# NN22_IMU_Adapter00_s00.net
KiCad netlist of a schematic drawn in EAGLE
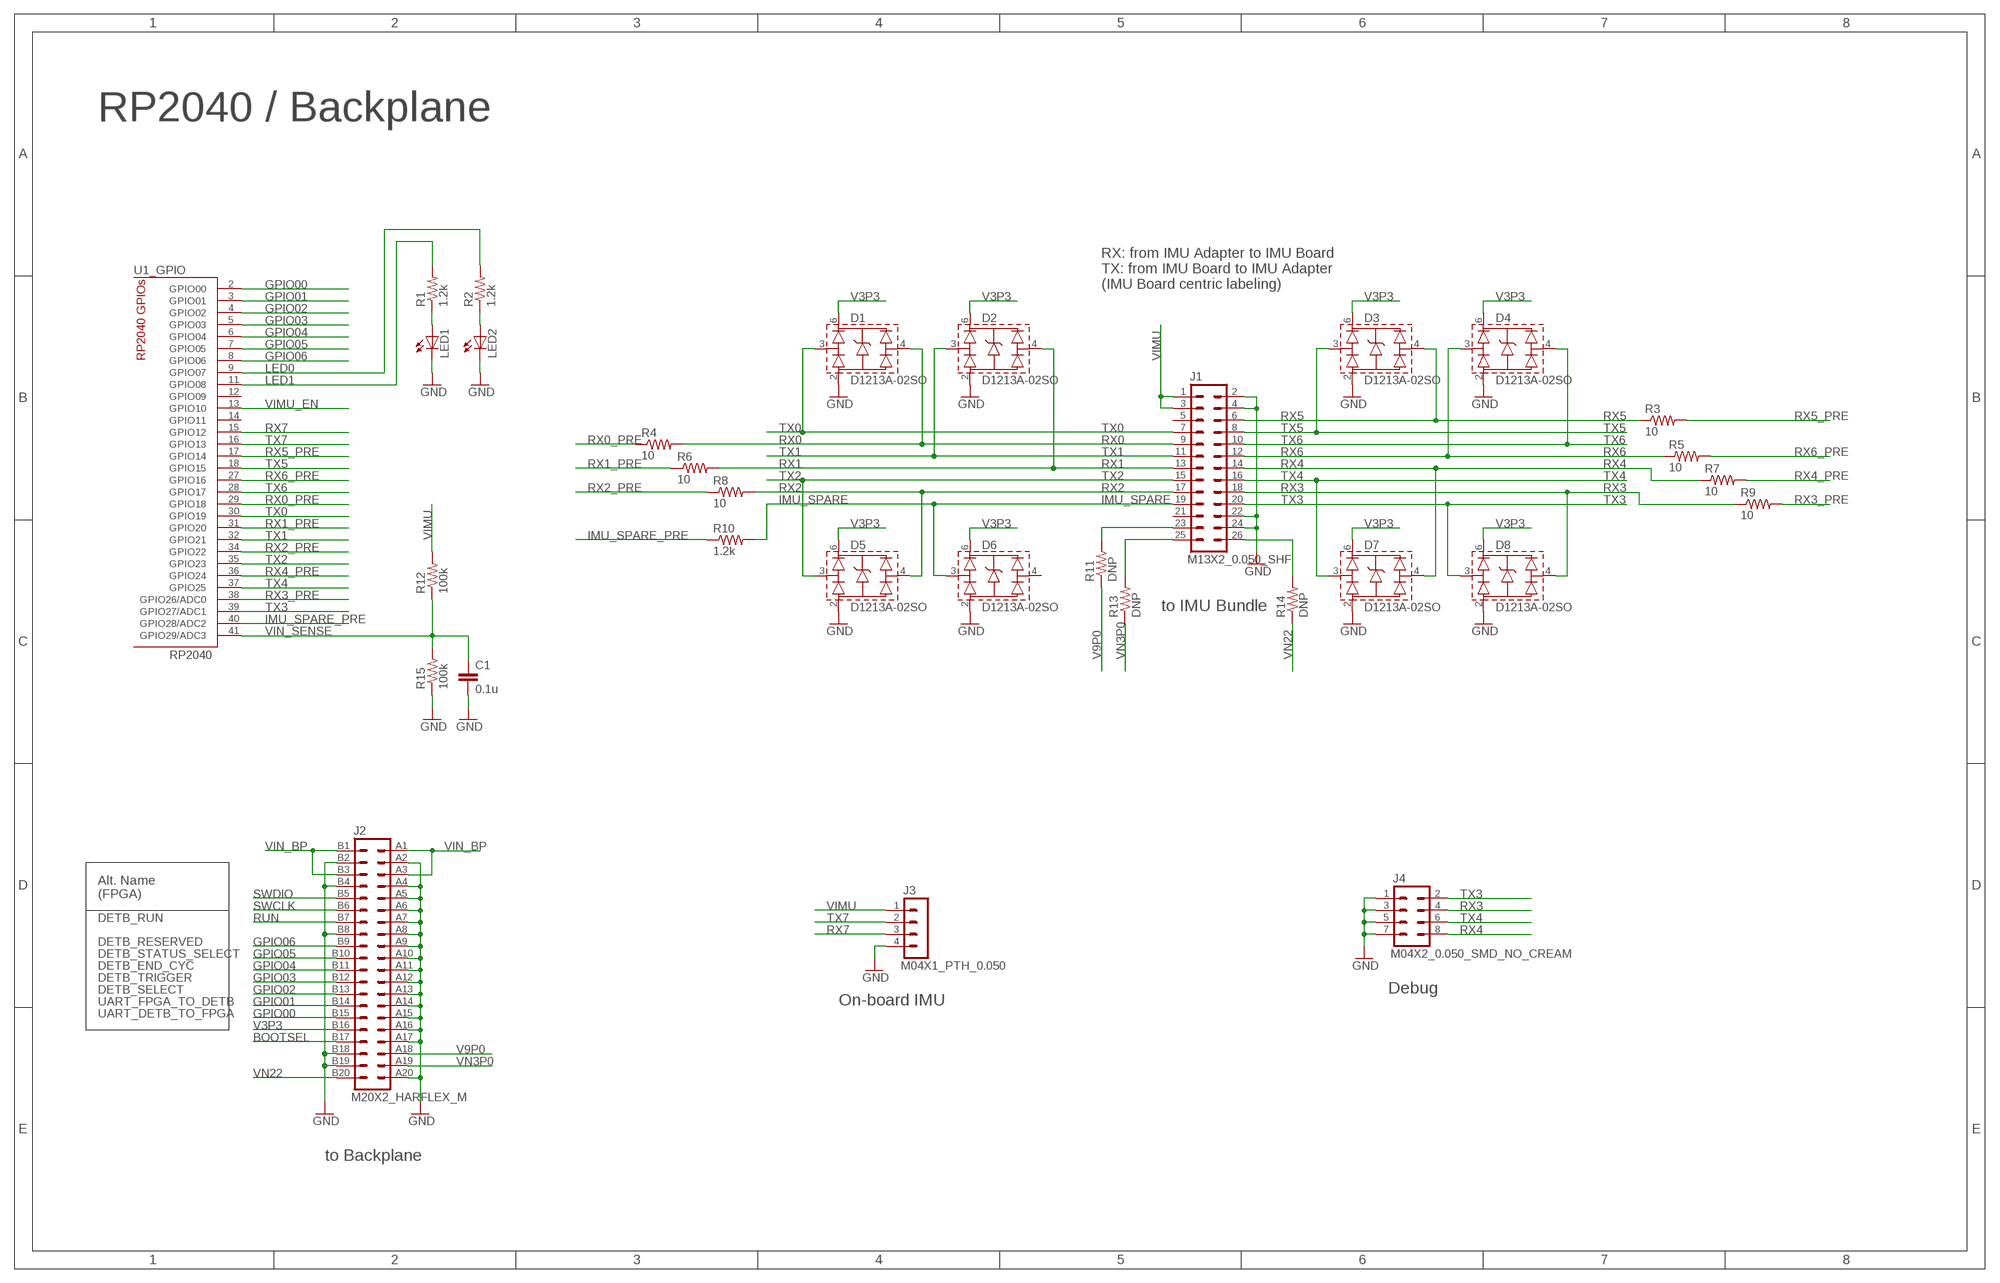
[diagram p0: schematic, sheet 1]
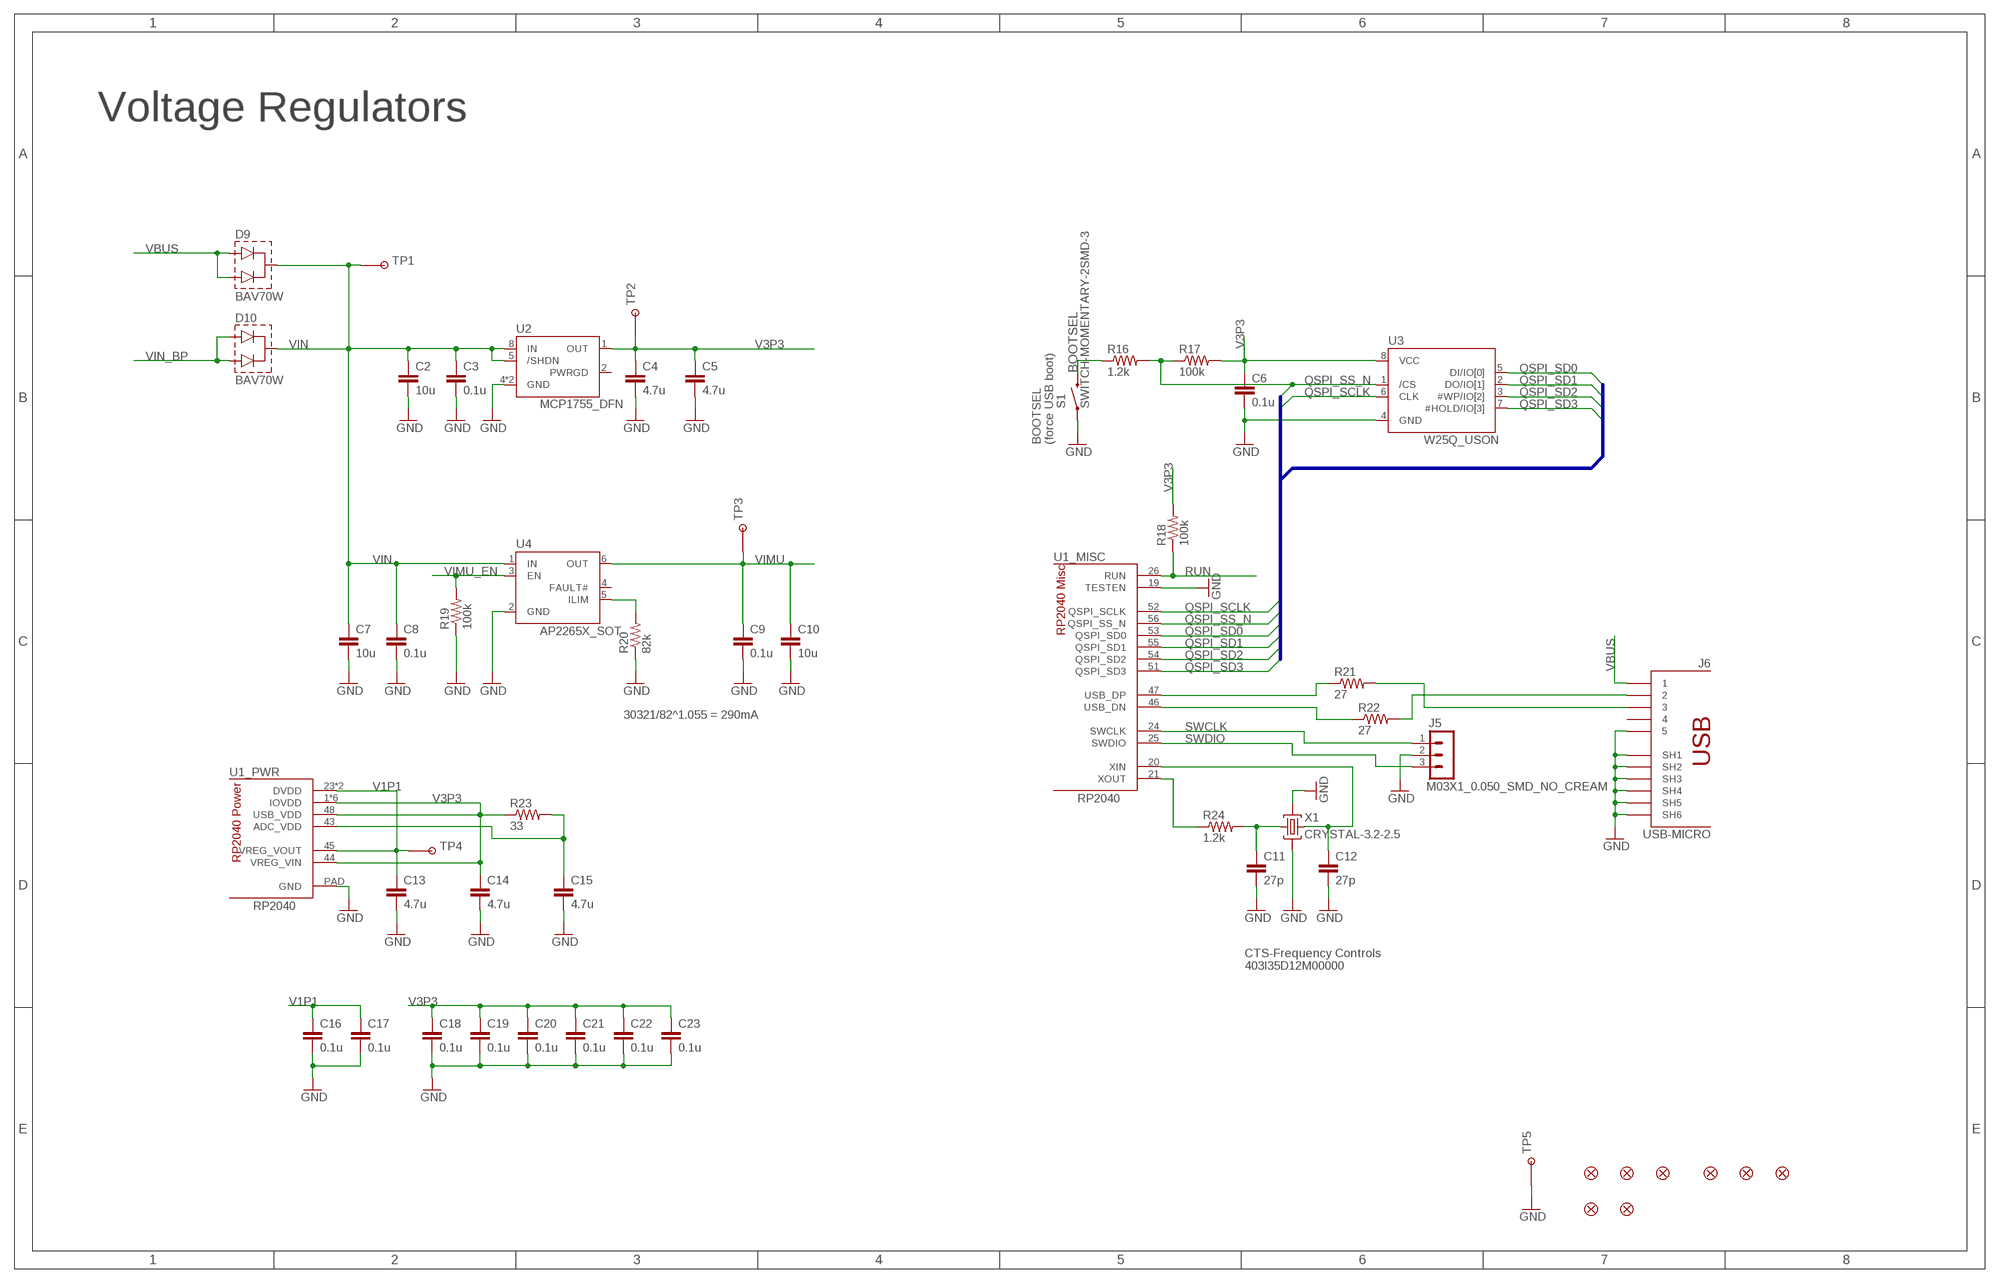
[diagram p1: schematic, sheet 2]

(export (version "E")
  (design (tool "Eeschema 10.0.6"))
  (components
    (comp (ref "C1")
      (value "0.1u")
      (footprint "eagle-import:0402-CAP")
      (libsource (lib "eagle-import") (part "CAP0402-CAP"))
    )
    (comp (ref "D1")
      (value "D1213A-02SO")
      (footprint "eagle-import:SOT23-6")
      (libsource (lib "eagle-import") (part "D1213A-02SO"))
    )
    (comp (ref "D2")
      (value "D1213A-02SO")
      (footprint "eagle-import:SOT23-6")
      (libsource (lib "eagle-import") (part "D1213A-02SO"))
    )
    (comp (ref "D3")
      (value "D1213A-02SO")
      (footprint "eagle-import:SOT23-6")
      (libsource (lib "eagle-import") (part "D1213A-02SO"))
    )
    (comp (ref "D4")
      (value "D1213A-02SO")
      (footprint "eagle-import:SOT23-6")
      (libsource (lib "eagle-import") (part "D1213A-02SO"))
    )
    (comp (ref "D5")
      (value "D1213A-02SO")
      (footprint "eagle-import:SOT23-6")
      (libsource (lib "eagle-import") (part "D1213A-02SO"))
    )
    (comp (ref "D6")
      (value "D1213A-02SO")
      (footprint "eagle-import:SOT23-6")
      (libsource (lib "eagle-import") (part "D1213A-02SO"))
    )
    (comp (ref "D7")
      (value "D1213A-02SO")
      (footprint "eagle-import:SOT23-6")
      (libsource (lib "eagle-import") (part "D1213A-02SO"))
    )
    (comp (ref "D8")
      (value "D1213A-02SO")
      (footprint "eagle-import:SOT23-6")
      (libsource (lib "eagle-import") (part "D1213A-02SO"))
    )
    (comp (ref "J1")
      (value "M13X2_0.050_SHF")
      (footprint "eagle-import:M13X2_0.050_SHF")
      (libsource (lib "eagle-import") (part "M13X2_0.050_SHF"))
    )
    (comp (ref "J2")
      (value "M20X2_HARFLEX_M")
      (footprint "eagle-import:M20X2_HARFLEX_M")
      (libsource (lib "eagle-import") (part "M20X2_HARFLEX_M"))
    )
    (comp (ref "J3")
      (value "M04X1_PTH_0.050")
      (footprint "eagle-import:M04X1_0.050_PTH")
      (libsource (lib "eagle-import") (part "M04X1_PTH_0.050"))
    )
    (comp (ref "J4")
      (value "M04X2_0.050_SMD_NO_CREAM")
      (footprint "eagle-import:M04X2_0.050_SMD_NO_CREAM")
      (libsource (lib "eagle-import") (part "M04X2_0.050_SMD_NO_CREAM"))
    )
    (comp (ref "LED1")
      (value "LED0603")
      (footprint "eagle-import:LED-0603")
      (libsource (lib "eagle-import") (part "LED0603"))
    )
    (comp (ref "LED2")
      (value "LED0603")
      (footprint "eagle-import:LED-0603")
      (libsource (lib "eagle-import") (part "LED0603"))
    )
    (comp (ref "R1")
      (value "1.2k")
      (footprint "eagle-import:0402-RES")
      (libsource (lib "eagle-import") (part "RESISTOR0402-RES"))
    )
    (comp (ref "R2")
      (value "1.2k")
      (footprint "eagle-import:0402-RES")
      (libsource (lib "eagle-import") (part "RESISTOR0402-RES"))
    )
    (comp (ref "R3")
      (value "10")
      (footprint "eagle-import:0402-RES")
      (libsource (lib "eagle-import") (part "RESISTOR0402-RES"))
    )
    (comp (ref "R4")
      (value "10")
      (footprint "eagle-import:0402-RES")
      (libsource (lib "eagle-import") (part "RESISTOR0402-RES"))
    )
    (comp (ref "R5")
      (value "10")
      (footprint "eagle-import:0402-RES")
      (libsource (lib "eagle-import") (part "RESISTOR0402-RES"))
    )
    (comp (ref "R6")
      (value "10")
      (footprint "eagle-import:0402-RES")
      (libsource (lib "eagle-import") (part "RESISTOR0402-RES"))
    )
    (comp (ref "R7")
      (value "10")
      (footprint "eagle-import:0402-RES")
      (libsource (lib "eagle-import") (part "RESISTOR0402-RES"))
    )
    (comp (ref "R8")
      (value "10")
      (footprint "eagle-import:0402-RES")
      (libsource (lib "eagle-import") (part "RESISTOR0402-RES"))
    )
    (comp (ref "R9")
      (value "10")
      (footprint "eagle-import:0402-RES")
      (libsource (lib "eagle-import") (part "RESISTOR0402-RES"))
    )
    (comp (ref "R10")
      (value "1.2k")
      (footprint "eagle-import:0402-RES")
      (libsource (lib "eagle-import") (part "RESISTOR0402-RES"))
    )
    (comp (ref "R11")
      (value "DNP")
      (footprint "eagle-import:0603-RES")
      (libsource (lib "eagle-import") (part "RESISTOR0603-RES"))
    )
    (comp (ref "R12")
      (value "100k")
      (footprint "eagle-import:0402-RES")
      (libsource (lib "eagle-import") (part "RESISTOR0402-RES"))
    )
    (comp (ref "R13")
      (value "DNP")
      (footprint "eagle-import:0603-RES")
      (libsource (lib "eagle-import") (part "RESISTOR0603-RES"))
    )
    (comp (ref "R14")
      (value "DNP")
      (footprint "eagle-import:0603-RES")
      (libsource (lib "eagle-import") (part "RESISTOR0603-RES"))
    )
    (comp (ref "R15")
      (value "100k")
      (footprint "eagle-import:0402-RES")
      (libsource (lib "eagle-import") (part "RESISTOR0402-RES"))
    )
    (comp (ref "U1")
      (value "RP2040")
      (footprint "eagle-import:QFN-56_EP")
      (libsource (lib "eagle-import") (part "RP2040"))
    )
    (comp (ref "C2")
      (value "10u")
      (footprint "eagle-import:0603-CAP")
      (libsource (lib "eagle-import") (part "CAP0603-CAP"))
    )
    (comp (ref "C3")
      (value "0.1u")
      (footprint "eagle-import:0402-CAP")
      (libsource (lib "eagle-import") (part "CAP0402-CAP"))
    )
    (comp (ref "C4")
      (value "4.7u")
      (footprint "eagle-import:0402-CAP")
      (libsource (lib "eagle-import") (part "CAP0402-CAP"))
    )
    (comp (ref "C5")
      (value "4.7u")
      (footprint "eagle-import:0402-CAP")
      (libsource (lib "eagle-import") (part "CAP0402-CAP"))
    )
    (comp (ref "C6")
      (value "0.1u")
      (footprint "eagle-import:0402-CAP")
      (libsource (lib "eagle-import") (part "CAP0402-CAP"))
    )
    (comp (ref "C7")
      (value "10u")
      (footprint "eagle-import:0603-CAP")
      (libsource (lib "eagle-import") (part "CAP0603-CAP"))
    )
    (comp (ref "C8")
      (value "0.1u")
      (footprint "eagle-import:0402-CAP")
      (libsource (lib "eagle-import") (part "CAP0402-CAP"))
    )
    (comp (ref "C9")
      (value "0.1u")
      (footprint "eagle-import:0402-CAP")
      (libsource (lib "eagle-import") (part "CAP0402-CAP"))
    )
    (comp (ref "C10")
      (value "10u")
      (footprint "eagle-import:0603-CAP")
      (libsource (lib "eagle-import") (part "CAP0603-CAP"))
    )
    (comp (ref "C11")
      (value "27p")
      (footprint "eagle-import:0402-CAP")
      (libsource (lib "eagle-import") (part "CAP0402-CAP"))
    )
    (comp (ref "C12")
      (value "27p")
      (footprint "eagle-import:0402-CAP")
      (libsource (lib "eagle-import") (part "CAP0402-CAP"))
    )
    (comp (ref "C13")
      (value "4.7u")
      (footprint "eagle-import:0402-CAP")
      (libsource (lib "eagle-import") (part "CAP0402-CAP"))
    )
    (comp (ref "C14")
      (value "4.7u")
      (footprint "eagle-import:0402-CAP")
      (libsource (lib "eagle-import") (part "CAP0402-CAP"))
    )
    (comp (ref "C15")
      (value "4.7u")
      (footprint "eagle-import:0402-CAP")
      (libsource (lib "eagle-import") (part "CAP0402-CAP"))
    )
    (comp (ref "C16")
      (value "0.1u")
      (footprint "eagle-import:0402-CAP")
      (libsource (lib "eagle-import") (part "CAP0402-CAP"))
    )
    (comp (ref "C17")
      (value "0.1u")
      (footprint "eagle-import:0402-CAP")
      (libsource (lib "eagle-import") (part "CAP0402-CAP"))
    )
    (comp (ref "C18")
      (value "0.1u")
      (footprint "eagle-import:0402-CAP")
      (libsource (lib "eagle-import") (part "CAP0402-CAP"))
    )
    (comp (ref "C19")
      (value "0.1u")
      (footprint "eagle-import:0402-CAP")
      (libsource (lib "eagle-import") (part "CAP0402-CAP"))
    )
    (comp (ref "C20")
      (value "0.1u")
      (footprint "eagle-import:0402-CAP")
      (libsource (lib "eagle-import") (part "CAP0402-CAP"))
    )
    (comp (ref "C21")
      (value "0.1u")
      (footprint "eagle-import:0402-CAP")
      (libsource (lib "eagle-import") (part "CAP0402-CAP"))
    )
    (comp (ref "C22")
      (value "0.1u")
      (footprint "eagle-import:0402-CAP")
      (libsource (lib "eagle-import") (part "CAP0402-CAP"))
    )
    (comp (ref "C23")
      (value "0.1u")
      (footprint "eagle-import:0402-CAP")
      (libsource (lib "eagle-import") (part "CAP0402-CAP"))
    )
    (comp (ref "D9")
      (value "BAV70W")
      (footprint "eagle-import:SOT323")
      (libsource (lib "eagle-import") (part "DIODE-COMMON_CATHODE_SOT323"))
    )
    (comp (ref "D10")
      (value "BAV70W")
      (footprint "eagle-import:SOT323")
      (libsource (lib "eagle-import") (part "DIODE-COMMON_CATHODE_SOT323"))
    )
    (comp (ref "FID1")
      (value "FIDUCIALUFIDUCIAL")
      (footprint "eagle-import:MICRO-FIDUCIAL")
      (libsource (lib "eagle-import") (part "FIDUCIALUFIDUCIAL"))
    )
    (comp (ref "FID2")
      (value "FIDUCIALUFIDUCIAL")
      (footprint "eagle-import:MICRO-FIDUCIAL")
      (libsource (lib "eagle-import") (part "FIDUCIALUFIDUCIAL"))
    )
    (comp (ref "FID3")
      (value "FIDUCIALUFIDUCIAL")
      (footprint "eagle-import:MICRO-FIDUCIAL")
      (libsource (lib "eagle-import") (part "FIDUCIALUFIDUCIAL"))
    )
    (comp (ref "FID4")
      (value "FIDUCIALUFIDUCIAL")
      (footprint "eagle-import:MICRO-FIDUCIAL")
      (libsource (lib "eagle-import") (part "FIDUCIALUFIDUCIAL"))
    )
    (comp (ref "FID5")
      (value "FIDUCIALUFIDUCIAL")
      (footprint "eagle-import:MICRO-FIDUCIAL")
      (libsource (lib "eagle-import") (part "FIDUCIALUFIDUCIAL"))
    )
    (comp (ref "FID6")
      (value "FIDUCIALUFIDUCIAL")
      (footprint "eagle-import:MICRO-FIDUCIAL")
      (libsource (lib "eagle-import") (part "FIDUCIALUFIDUCIAL"))
    )
    (comp (ref "FID7")
      (value "FIDUCIALUFIDUCIAL")
      (footprint "eagle-import:MICRO-FIDUCIAL")
      (libsource (lib "eagle-import") (part "FIDUCIALUFIDUCIAL"))
    )
    (comp (ref "FID8")
      (value "FIDUCIALUFIDUCIAL")
      (footprint "eagle-import:MICRO-FIDUCIAL")
      (libsource (lib "eagle-import") (part "FIDUCIALUFIDUCIAL"))
    )
    (comp (ref "J5")
      (value "M03X1_0.050_SMD_NO_CREAM")
      (footprint "eagle-import:M03X1_0.050_SMD_NO_CREAM")
      (libsource (lib "eagle-import") (part "M03X1_0.050_SMD_NO_CREAM"))
    )
    (comp (ref "J6")
      (value "USB-MICRO")
      (footprint "eagle-import:USB-MICRO")
      (libsource (lib "eagle-import") (part "USB-MICRO"))
    )
    (comp (ref "R16")
      (value "1.2k")
      (footprint "eagle-import:0402-RES")
      (libsource (lib "eagle-import") (part "RESISTOR0402-RES"))
    )
    (comp (ref "R17")
      (value "100k")
      (footprint "eagle-import:0402-RES")
      (libsource (lib "eagle-import") (part "RESISTOR0402-RES"))
    )
    (comp (ref "R18")
      (value "100k")
      (footprint "eagle-import:0402-RES")
      (libsource (lib "eagle-import") (part "RESISTOR0402-RES"))
    )
    (comp (ref "R19")
      (value "100k")
      (footprint "eagle-import:0402-RES")
      (libsource (lib "eagle-import") (part "RESISTOR0402-RES"))
    )
    (comp (ref "R20")
      (value "82k")
      (footprint "eagle-import:0402-RES")
      (libsource (lib "eagle-import") (part "RESISTOR0402-RES"))
    )
    (comp (ref "R21")
      (value "27")
      (footprint "eagle-import:0402-RES")
      (libsource (lib "eagle-import") (part "RESISTOR0402-RES"))
    )
    (comp (ref "R22")
      (value "27")
      (footprint "eagle-import:0402-RES")
      (libsource (lib "eagle-import") (part "RESISTOR0402-RES"))
    )
    (comp (ref "R23")
      (value "33")
      (footprint "eagle-import:0402-RES")
      (libsource (lib "eagle-import") (part "RESISTOR0402-RES"))
    )
    (comp (ref "R24")
      (value "1.2k")
      (footprint "eagle-import:0402-RES")
      (libsource (lib "eagle-import") (part "RESISTOR0402-RES"))
    )
    (comp (ref "S1")
      (value "SWITCH-MOMENTARY-2SMD-3")
      (footprint "eagle-import:TACTILE_SWITCH_SMD-3")
      (libsource (lib "eagle-import") (part "SWITCH-MOMENTARY-2SMD-3"))
    )
    (comp (ref "TP1")
      (value "TESTPOINT_ROUND")
      (footprint "eagle-import:TESTPAD_ROUND")
      (libsource (lib "eagle-import") (part "TESTPOINT_ROUND"))
    )
    (comp (ref "TP2")
      (value "TESTPOINT_ROUND")
      (footprint "eagle-import:TESTPAD_ROUND")
      (libsource (lib "eagle-import") (part "TESTPOINT_ROUND"))
    )
    (comp (ref "TP3")
      (value "TESTPOINT_ROUND")
      (footprint "eagle-import:TESTPAD_ROUND")
      (libsource (lib "eagle-import") (part "TESTPOINT_ROUND"))
    )
    (comp (ref "TP4")
      (value "TESTPOINTPADSMALL")
      (footprint "eagle-import:TESTPAD_SMALL")
      (libsource (lib "eagle-import") (part "TESTPOINTPADSMALL"))
    )
    (comp (ref "TP5")
      (value "TESTPOINT1X01")
      (footprint "eagle-import:1X01")
      (libsource (lib "eagle-import") (part "TESTPOINT1X01"))
    )
    (comp (ref "U2")
      (value "MCP1755_DFN")
      (footprint "eagle-import:DFN8_2X3MM")
      (libsource (lib "eagle-import") (part "MCP1755_DFN"))
    )
    (comp (ref "U3")
      (value "W25Q_USON")
      (footprint "eagle-import:USON8L-2X3MM")
      (libsource (lib "eagle-import") (part "W25Q_USON"))
    )
    (comp (ref "U4")
      (value "AP2265X_SOT")
      (footprint "eagle-import:SOT23-6")
      (libsource (lib "eagle-import") (part "AP2265X_SOT"))
    )
    (comp (ref "X1")
      (value "CRYSTAL-3.2-2.5")
      (footprint "eagle-import:CRYSTAL-3.2-2.5")
      (libsource (lib "eagle-import") (part "CRYSTAL-3.2-2.5"))
    )
  )
  (nets
    (net (code "1") (name "BOOTSEL") (class "Default")
      (node (ref "J2") (pin "B17") (pinfunction "33_B17") (pintype "passive"))
      (node (ref "R16") (pin "1") (pinfunction "1_1") (pintype "passive"))
      (node (ref "S1") (pin "4") (pinfunction "2_4") (pintype "passive"))
    )
    (net (code "2") (name "GND") (class "Default")
      (node (ref "C1") (pin "2") (pinfunction "2_2") (pintype "passive"))
      (node (ref "C10") (pin "2") (pinfunction "2_2") (pintype "passive"))
      (node (ref "C11") (pin "2") (pinfunction "2_2") (pintype "passive"))
      (node (ref "C12") (pin "2") (pinfunction "2_2") (pintype "passive"))
      (node (ref "C13") (pin "2") (pinfunction "2_2") (pintype "passive"))
      (node (ref "C14") (pin "2") (pinfunction "2_2") (pintype "passive"))
      (node (ref "C15") (pin "2") (pinfunction "2_2") (pintype "passive"))
      (node (ref "C16") (pin "2") (pinfunction "2_2") (pintype "passive"))
      (node (ref "C17") (pin "2") (pinfunction "2_2") (pintype "passive"))
      (node (ref "C18") (pin "2") (pinfunction "2_2") (pintype "passive"))
      (node (ref "C19") (pin "2") (pinfunction "2_2") (pintype "passive"))
      (node (ref "C2") (pin "2") (pinfunction "2_2") (pintype "passive"))
      (node (ref "C20") (pin "2") (pinfunction "2_2") (pintype "passive"))
      (node (ref "C21") (pin "2") (pinfunction "2_2") (pintype "passive"))
      (node (ref "C22") (pin "2") (pinfunction "2_2") (pintype "passive"))
      (node (ref "C23") (pin "2") (pinfunction "2_2") (pintype "passive"))
      (node (ref "C3") (pin "2") (pinfunction "2_2") (pintype "passive"))
      (node (ref "C4") (pin "2") (pinfunction "2_2") (pintype "passive"))
      (node (ref "C5") (pin "2") (pinfunction "2_2") (pintype "passive"))
      (node (ref "C6") (pin "2") (pinfunction "2_2") (pintype "passive"))
      (node (ref "C7") (pin "2") (pinfunction "2_2") (pintype "passive"))
      (node (ref "C8") (pin "2") (pinfunction "2_2") (pintype "passive"))
      (node (ref "C9") (pin "2") (pinfunction "2_2") (pintype "passive"))
      (node (ref "D1") (pin "2") (pinfunction "VN_2") (pintype "power_in"))
      (node (ref "D2") (pin "2") (pinfunction "VN_2") (pintype "power_in"))
      (node (ref "D3") (pin "2") (pinfunction "VN_2") (pintype "power_in"))
      (node (ref "D4") (pin "2") (pinfunction "VN_2") (pintype "power_in"))
      (node (ref "D5") (pin "2") (pinfunction "VN_2") (pintype "power_in"))
      (node (ref "D6") (pin "2") (pinfunction "VN_2") (pintype "power_in"))
      (node (ref "D7") (pin "2") (pinfunction "VN_2") (pintype "power_in"))
      (node (ref "D8") (pin "2") (pinfunction "VN_2") (pintype "power_in"))
      (node (ref "J1") (pin "2") (pinfunction "2_2") (pintype "passive"))
      (node (ref "J1") (pin "22") (pinfunction "22_22") (pintype "passive"))
      (node (ref "J1") (pin "24") (pinfunction "24_24") (pintype "passive"))
      (node (ref "J1") (pin "4") (pinfunction "4_4") (pintype "passive"))
      (node (ref "J2") (pin "A10") (pinfunction "20_A10") (pintype "passive"))
      (node (ref "J2") (pin "A11") (pinfunction "22_A11") (pintype "passive"))
      (node (ref "J2") (pin "A12") (pinfunction "24_A12") (pintype "passive"))
      (node (ref "J2") (pin "A13") (pinfunction "26_A13") (pintype "passive"))
      (node (ref "J2") (pin "A14") (pinfunction "28_A14") (pintype "passive"))
      (node (ref "J2") (pin "A15") (pinfunction "30_A15") (pintype "passive"))
      (node (ref "J2") (pin "A16") (pinfunction "32_A16") (pintype "passive"))
      (node (ref "J2") (pin "A17") (pinfunction "34_A17") (pintype "passive"))
      (node (ref "J2") (pin "A2") (pinfunction "4_A2") (pintype "passive"))
      (node (ref "J2") (pin "A20") (pinfunction "40_A20") (pintype "passive"))
      (node (ref "J2") (pin "A4") (pinfunction "8_A4") (pintype "passive"))
      (node (ref "J2") (pin "A5") (pinfunction "10_A5") (pintype "passive"))
      (node (ref "J2") (pin "A6") (pinfunction "12_A6") (pintype "passive"))
      (node (ref "J2") (pin "A7") (pinfunction "14_A7") (pintype "passive"))
      (node (ref "J2") (pin "A8") (pinfunction "16_A8") (pintype "passive"))
      (node (ref "J2") (pin "A9") (pinfunction "18_A9") (pintype "passive"))
      (node (ref "J2") (pin "B18") (pinfunction "35_B18") (pintype "passive"))
      (node (ref "J2") (pin "B19") (pinfunction "37_B19") (pintype "passive"))
      (node (ref "J2") (pin "B2") (pinfunction "3_B2") (pintype "passive"))
      (node (ref "J2") (pin "B4") (pinfunction "7_B4") (pintype "passive"))
      (node (ref "J2") (pin "B8") (pinfunction "15_B8") (pintype "passive"))
      (node (ref "J3") (pin "4") (pinfunction "4_4") (pintype "passive"))
      (node (ref "J4") (pin "1") (pinfunction "1_1") (pintype "passive"))
      (node (ref "J4") (pin "3") (pinfunction "3_3") (pintype "passive"))
      (node (ref "J4") (pin "5") (pinfunction "5_5") (pintype "passive"))
      (node (ref "J4") (pin "7") (pinfunction "7_7") (pintype "passive"))
      (node (ref "J5") (pin "2") (pinfunction "2_2") (pintype "passive"))
      (node (ref "J6") (pin "5") (pinfunction "5_5") (pintype "bidirectional"))
      (node (ref "J6") (pin "SH1") (pinfunction "SH1_SH1") (pintype "bidirectional"))
      (node (ref "J6") (pin "SH2") (pinfunction "SH2_SH2") (pintype "bidirectional"))
      (node (ref "J6") (pin "SH3") (pinfunction "SH3_SH3") (pintype "bidirectional"))
      (node (ref "J6") (pin "SH4") (pinfunction "SH4_SH4") (pintype "bidirectional"))
      (node (ref "J6") (pin "SH5") (pinfunction "SH5_SH5") (pintype "bidirectional"))
      (node (ref "J6") (pin "SH6") (pinfunction "SH6_SH6") (pintype "bidirectional"))
      (node (ref "LED1") (pin "C") (pinfunction "C_C") (pintype "passive"))
      (node (ref "LED2") (pin "C") (pinfunction "C_C") (pintype "passive"))
      (node (ref "R15") (pin "1") (pinfunction "1_1") (pintype "passive"))
      (node (ref "R19") (pin "1") (pinfunction "1_1") (pintype "passive"))
      (node (ref "R20") (pin "1") (pinfunction "1_1") (pintype "passive"))
      (node (ref "S1") (pin "1") (pinfunction "1_1") (pintype "passive"))
      (node (ref "TP5") (pin "1") (pinfunction "P$1_1") (pintype "bidirectional"))
      (node (ref "U1") (pin "19") (pinfunction "TESTEN_19") (pintype "input"))
      (node (ref "U1") (pin "PAD") (pinfunction "GND_PAD") (pintype "power_in"))
      (node (ref "U2") (pin "4") (pinfunction "GND_4") (pintype "power_in"))
      (node (ref "U2") (pin "P") (pinfunction "GND_P") (pintype "power_in"))
      (node (ref "U3") (pin "4") (pinfunction "GND_4") (pintype "power_in"))
      (node (ref "U4") (pin "2") (pinfunction "GND_2") (pintype "power_in"))
      (node (ref "X1") (pin "2") (pinfunction "GND_2") (pintype "passive"))
      (node (ref "X1") (pin "4") (pinfunction "GND_4") (pintype "passive"))
    )
    (net (code "3") (name "GPIO00") (class "Default")
      (node (ref "J2") (pin "B15") (pinfunction "29_B15") (pintype "passive"))
      (node (ref "U1") (pin "2") (pinfunction "GPIO00_2") (pintype "bidirectional"))
    )
    (net (code "4") (name "GPIO01") (class "Default")
      (node (ref "J2") (pin "B14") (pinfunction "27_B14") (pintype "passive"))
      (node (ref "U1") (pin "3") (pinfunction "GPIO01_3") (pintype "bidirectional"))
    )
    (net (code "5") (name "GPIO02") (class "Default")
      (node (ref "J2") (pin "B13") (pinfunction "25_B13") (pintype "passive"))
      (node (ref "U1") (pin "4") (pinfunction "GPIO02_4") (pintype "bidirectional"))
    )
    (net (code "6") (name "GPIO03") (class "Default")
      (node (ref "J2") (pin "B12") (pinfunction "23_B12") (pintype "passive"))
      (node (ref "U1") (pin "5") (pinfunction "GPIO03_5") (pintype "bidirectional"))
    )
    (net (code "7") (name "GPIO04") (class "Default")
      (node (ref "J2") (pin "B11") (pinfunction "21_B11") (pintype "passive"))
      (node (ref "U1") (pin "6") (pinfunction "GPIO04_6") (pintype "bidirectional"))
    )
    (net (code "8") (name "GPIO05") (class "Default")
      (node (ref "J2") (pin "B10") (pinfunction "19_B10") (pintype "passive"))
      (node (ref "U1") (pin "7") (pinfunction "GPIO05_7") (pintype "bidirectional"))
    )
    (net (code "9") (name "GPIO06") (class "Default")
      (node (ref "J2") (pin "B9") (pinfunction "17_B9") (pintype "passive"))
      (node (ref "U1") (pin "8") (pinfunction "GPIO06_8") (pintype "bidirectional"))
    )
    (net (code "10") (name "IMU_SPARE") (class "Default")
      (node (ref "D6") (pin "3") (pinfunction "CH1_3") (pintype "bidirectional"))
      (node (ref "J1") (pin "19") (pinfunction "19_19") (pintype "passive"))
      (node (ref "R10") (pin "2") (pinfunction "2_2") (pintype "passive"))
    )
    (net (code "11") (name "IMU_SPARE_PRE") (class "Default")
      (node (ref "R10") (pin "1") (pinfunction "1_1") (pintype "passive"))
      (node (ref "U1") (pin "40") (pinfunction "GPIO28/ADC2_40") (pintype "bidirectional"))
    )
    (net (code "12") (name "LED0") (class "Default")
      (node (ref "R2") (pin "2") (pinfunction "2_2") (pintype "passive"))
      (node (ref "U1") (pin "9") (pinfunction "GPIO07_9") (pintype "bidirectional"))
    )
    (net (code "13") (name "LED1") (class "Default")
      (node (ref "R1") (pin "2") (pinfunction "2_2") (pintype "passive"))
      (node (ref "U1") (pin "11") (pinfunction "GPIO08_11") (pintype "bidirectional"))
    )
    (net (code "14") (name "Net-(J1-Pad23)") (class "Default")
      (node (ref "J1") (pin "23") (pinfunction "23_23") (pintype "passive"))
      (node (ref "R11") (pin "2") (pinfunction "2_2") (pintype "passive"))
    )
    (net (code "15") (name "Net-(J1-Pad25)") (class "Default")
      (node (ref "J1") (pin "25") (pinfunction "25_25") (pintype "passive"))
      (node (ref "R13") (pin "2") (pinfunction "2_2") (pintype "passive"))
    )
    (net (code "16") (name "Net-(J1-Pad26)") (class "Default")
      (node (ref "J1") (pin "26") (pinfunction "26_26") (pintype "passive"))
      (node (ref "R14") (pin "2") (pinfunction "2_2") (pintype "passive"))
    )
    (net (code "17") (name "Net-(J6-Pad2)") (class "Default")
      (node (ref "J6") (pin "2") (pinfunction "2_2") (pintype "bidirectional"))
      (node (ref "R22") (pin "2") (pinfunction "2_2") (pintype "passive"))
    )
    (net (code "18") (name "Net-(J6-Pad3)") (class "Default")
      (node (ref "J6") (pin "3") (pinfunction "3_3") (pintype "bidirectional"))
      (node (ref "R21") (pin "2") (pinfunction "2_2") (pintype "passive"))
    )
    (net (code "19") (name "Net-(LED1-PadA)") (class "Default")
      (node (ref "LED1") (pin "A") (pinfunction "A_A") (pintype "passive"))
      (node (ref "R1") (pin "1") (pinfunction "1_1") (pintype "passive"))
    )
    (net (code "20") (name "Net-(LED2-PadA)") (class "Default")
      (node (ref "LED2") (pin "A") (pinfunction "A_A") (pintype "passive"))
      (node (ref "R2") (pin "1") (pinfunction "1_1") (pintype "passive"))
    )
    (net (code "21") (name "Net-(U1B-USB_DN)") (class "Default")
      (node (ref "R22") (pin "1") (pinfunction "1_1") (pintype "passive"))
      (node (ref "U1") (pin "46") (pinfunction "USB_DN_46") (pintype "bidirectional"))
    )
    (net (code "22") (name "Net-(U1B-USB_DP)") (class "Default")
      (node (ref "R21") (pin "1") (pinfunction "1_1") (pintype "passive"))
      (node (ref "U1") (pin "47") (pinfunction "USB_DP_47") (pintype "bidirectional"))
    )
    (net (code "23") (name "Net-(U1B-XIN)") (class "Default")
      (node (ref "C12") (pin "1") (pinfunction "1_1") (pintype "passive"))
      (node (ref "U1") (pin "20") (pinfunction "XIN_20") (pintype "bidirectional"))
      (node (ref "X1") (pin "3") (pinfunction "C2_3") (pintype "passive"))
    )
    (net (code "24") (name "Net-(U1B-XOUT)") (class "Default")
      (node (ref "R24") (pin "1") (pinfunction "1_1") (pintype "passive"))
      (node (ref "U1") (pin "21") (pinfunction "XOUT_21") (pintype "bidirectional"))
    )
    (net (code "25") (name "Net-(U1C-ADC_VDD)") (class "Default")
      (node (ref "C15") (pin "1") (pinfunction "1_1") (pintype "passive"))
      (node (ref "R23") (pin "2") (pinfunction "2_2") (pintype "passive"))
      (node (ref "U1") (pin "43") (pinfunction "ADC_VDD_43") (pintype "power_in"))
    )
    (net (code "26") (name "Net-(U4-ILIM)") (class "Default")
      (node (ref "R20") (pin "2") (pinfunction "2_2") (pintype "passive"))
      (node (ref "U4") (pin "5") (pinfunction "ILIM_5") (pintype "bidirectional"))
    )
    (net (code "27") (name "Net-(X1-C1)") (class "Default")
      (node (ref "C11") (pin "1") (pinfunction "1_1") (pintype "passive"))
      (node (ref "R24") (pin "2") (pinfunction "2_2") (pintype "passive"))
      (node (ref "X1") (pin "1") (pinfunction "C1_1") (pintype "passive"))
    )
    (net (code "28") (name "QSPI_SCLK") (class "Default")
      (node (ref "U1") (pin "52") (pinfunction "QSPI_SCLK_52") (pintype "output"))
      (node (ref "U3") (pin "6") (pinfunction "CLK_6") (pintype "input"))
    )
    (net (code "29") (name "QSPI_SD0") (class "Default")
      (node (ref "U1") (pin "53") (pinfunction "QSPI_SD0_53") (pintype "bidirectional"))
      (node (ref "U3") (pin "5") (pinfunction "DI/IO[0]_5") (pintype "bidirectional"))
    )
    (net (code "30") (name "QSPI_SD1") (class "Default")
      (node (ref "U1") (pin "55") (pinfunction "QSPI_SD1_55") (pintype "bidirectional"))
      (node (ref "U3") (pin "2") (pinfunction "DO/IO[1]_2") (pintype "bidirectional"))
    )
    (net (code "31") (name "QSPI_SD2") (class "Default")
      (node (ref "U1") (pin "54") (pinfunction "QSPI_SD2_54") (pintype "bidirectional"))
      (node (ref "U3") (pin "3") (pinfunction "#WP/IO[2]_3") (pintype "bidirectional"))
    )
    (net (code "32") (name "QSPI_SD3") (class "Default")
      (node (ref "U1") (pin "51") (pinfunction "QSPI_SD3_51") (pintype "bidirectional"))
      (node (ref "U3") (pin "7") (pinfunction "#HOLD/IO[3]_7") (pintype "bidirectional"))
    )
    (net (code "33") (name "QSPI_SS_N") (class "Default")
      (node (ref "R16") (pin "2") (pinfunction "2_2") (pintype "passive"))
      (node (ref "R17") (pin "1") (pinfunction "1_1") (pintype "passive"))
      (node (ref "U1") (pin "56") (pinfunction "QSPI_SS_N_56") (pintype "output"))
      (node (ref "U3") (pin "1") (pinfunction "/CS_1") (pintype "input"))
    )
    (net (code "34") (name "RUN") (class "Default")
      (node (ref "J2") (pin "B7") (pinfunction "13_B7") (pintype "passive"))
      (node (ref "R18") (pin "1") (pinfunction "1_1") (pintype "passive"))
      (node (ref "U1") (pin "26") (pinfunction "RUN_26") (pintype "input"))
    )
    (net (code "35") (name "RX0") (class "Default")
      (node (ref "D1") (pin "4") (pinfunction "CH2_4") (pintype "bidirectional"))
      (node (ref "J1") (pin "9") (pinfunction "9_9") (pintype "passive"))
      (node (ref "R4") (pin "2") (pinfunction "2_2") (pintype "passive"))
    )
    (net (code "36") (name "RX0_PRE") (class "Default")
      (node (ref "R4") (pin "1") (pinfunction "1_1") (pintype "passive"))
      (node (ref "U1") (pin "29") (pinfunction "GPIO18_29") (pintype "bidirectional"))
    )
    (net (code "37") (name "RX1") (class "Default")
      (node (ref "D2") (pin "4") (pinfunction "CH2_4") (pintype "bidirectional"))
      (node (ref "J1") (pin "13") (pinfunction "13_13") (pintype "passive"))
      (node (ref "R6") (pin "2") (pinfunction "2_2") (pintype "passive"))
    )
    (net (code "38") (name "RX1_PRE") (class "Default")
      (node (ref "R6") (pin "1") (pinfunction "1_1") (pintype "passive"))
      (node (ref "U1") (pin "31") (pinfunction "GPIO20_31") (pintype "bidirectional"))
    )
    (net (code "39") (name "RX2") (class "Default")
      (node (ref "D5") (pin "4") (pinfunction "CH2_4") (pintype "bidirectional"))
      (node (ref "J1") (pin "17") (pinfunction "17_17") (pintype "passive"))
      (node (ref "R8") (pin "2") (pinfunction "2_2") (pintype "passive"))
    )
    (net (code "40") (name "RX2_PRE") (class "Default")
      (node (ref "R8") (pin "1") (pinfunction "1_1") (pintype "passive"))
      (node (ref "U1") (pin "34") (pinfunction "GPIO22_34") (pintype "bidirectional"))
    )
    (net (code "41") (name "RX3") (class "Default")
      (node (ref "D8") (pin "4") (pinfunction "CH2_4") (pintype "bidirectional"))
      (node (ref "J1") (pin "18") (pinfunction "18_18") (pintype "passive"))
      (node (ref "J4") (pin "4") (pinfunction "4_4") (pintype "passive"))
      (node (ref "R9") (pin "1") (pinfunction "1_1") (pintype "passive"))
    )
    (net (code "42") (name "RX3_PRE") (class "Default")
      (node (ref "R9") (pin "2") (pinfunction "2_2") (pintype "passive"))
      (node (ref "U1") (pin "38") (pinfunction "GPIO26/ADC0_38") (pintype "bidirectional"))
    )
    (net (code "43") (name "RX4") (class "Default")
      (node (ref "D7") (pin "4") (pinfunction "CH2_4") (pintype "bidirectional"))
      (node (ref "J1") (pin "14") (pinfunction "14_14") (pintype "passive"))
      (node (ref "J4") (pin "8") (pinfunction "8_8") (pintype "passive"))
      (node (ref "R7") (pin "1") (pinfunction "1_1") (pintype "passive"))
    )
    (net (code "44") (name "RX4_PRE") (class "Default")
      (node (ref "R7") (pin "2") (pinfunction "2_2") (pintype "passive"))
      (node (ref "U1") (pin "36") (pinfunction "GPIO24_36") (pintype "bidirectional"))
    )
    (net (code "45") (name "RX5") (class "Default")
      (node (ref "D3") (pin "4") (pinfunction "CH2_4") (pintype "bidirectional"))
      (node (ref "J1") (pin "6") (pinfunction "6_6") (pintype "passive"))
      (node (ref "R3") (pin "1") (pinfunction "1_1") (pintype "passive"))
    )
    (net (code "46") (name "RX5_PRE") (class "Default")
      (node (ref "R3") (pin "2") (pinfunction "2_2") (pintype "passive"))
      (node (ref "U1") (pin "17") (pinfunction "GPIO14_17") (pintype "bidirectional"))
    )
    (net (code "47") (name "RX6") (class "Default")
      (node (ref "D4") (pin "3") (pinfunction "CH1_3") (pintype "bidirectional"))
      (node (ref "J1") (pin "12") (pinfunction "12_12") (pintype "passive"))
      (node (ref "R5") (pin "1") (pinfunction "1_1") (pintype "passive"))
    )
    (net (code "48") (name "RX6_PRE") (class "Default")
      (node (ref "R5") (pin "2") (pinfunction "2_2") (pintype "passive"))
      (node (ref "U1") (pin "27") (pinfunction "GPIO16_27") (pintype "bidirectional"))
    )
    (net (code "49") (name "RX7") (class "Default")
      (node (ref "J3") (pin "3") (pinfunction "3_3") (pintype "passive"))
      (node (ref "U1") (pin "15") (pinfunction "GPIO12_15") (pintype "bidirectional"))
    )
    (net (code "50") (name "SWCLK") (class "Default")
      (node (ref "J2") (pin "B6") (pinfunction "11_B6") (pintype "passive"))
      (node (ref "J5") (pin "1") (pinfunction "1_1") (pintype "passive"))
      (node (ref "U1") (pin "24") (pinfunction "SWCLK_24") (pintype "input"))
    )
    (net (code "51") (name "SWDIO") (class "Default")
      (node (ref "J2") (pin "B5") (pinfunction "9_B5") (pintype "passive"))
      (node (ref "J5") (pin "3") (pinfunction "3_3") (pintype "passive"))
      (node (ref "U1") (pin "25") (pinfunction "SWDIO_25") (pintype "bidirectional"))
    )
    (net (code "52") (name "TX0") (class "Default")
      (node (ref "D1") (pin "3") (pinfunction "CH1_3") (pintype "bidirectional"))
      (node (ref "J1") (pin "7") (pinfunction "7_7") (pintype "passive"))
      (node (ref "U1") (pin "30") (pinfunction "GPIO19_30") (pintype "bidirectional"))
    )
    (net (code "53") (name "TX1") (class "Default")
      (node (ref "D2") (pin "3") (pinfunction "CH1_3") (pintype "bidirectional"))
      (node (ref "J1") (pin "11") (pinfunction "11_11") (pintype "passive"))
      (node (ref "U1") (pin "32") (pinfunction "GPIO21_32") (pintype "bidirectional"))
    )
    (net (code "54") (name "TX2") (class "Default")
      (node (ref "D5") (pin "3") (pinfunction "CH1_3") (pintype "bidirectional"))
      (node (ref "J1") (pin "15") (pinfunction "15_15") (pintype "passive"))
      (node (ref "U1") (pin "35") (pinfunction "GPIO23_35") (pintype "bidirectional"))
    )
    (net (code "55") (name "TX3") (class "Default")
      (node (ref "D8") (pin "3") (pinfunction "CH1_3") (pintype "bidirectional"))
      (node (ref "J1") (pin "20") (pinfunction "20_20") (pintype "passive"))
      (node (ref "J4") (pin "2") (pinfunction "2_2") (pintype "passive"))
      (node (ref "U1") (pin "39") (pinfunction "GPIO27/ADC1_39") (pintype "bidirectional"))
    )
    (net (code "56") (name "TX4") (class "Default")
      (node (ref "D7") (pin "3") (pinfunction "CH1_3") (pintype "bidirectional"))
      (node (ref "J1") (pin "16") (pinfunction "16_16") (pintype "passive"))
      (node (ref "J4") (pin "6") (pinfunction "6_6") (pintype "passive"))
      (node (ref "U1") (pin "37") (pinfunction "GPIO25_37") (pintype "bidirectional"))
    )
    (net (code "57") (name "TX5") (class "Default")
      (node (ref "D3") (pin "3") (pinfunction "CH1_3") (pintype "bidirectional"))
      (node (ref "J1") (pin "8") (pinfunction "8_8") (pintype "passive"))
      (node (ref "U1") (pin "18") (pinfunction "GPIO15_18") (pintype "bidirectional"))
    )
    (net (code "58") (name "TX6") (class "Default")
      (node (ref "D4") (pin "4") (pinfunction "CH2_4") (pintype "bidirectional"))
      (node (ref "J1") (pin "10") (pinfunction "10_10") (pintype "passive"))
      (node (ref "U1") (pin "28") (pinfunction "GPIO17_28") (pintype "bidirectional"))
    )
    (net (code "59") (name "TX7") (class "Default")
      (node (ref "J3") (pin "2") (pinfunction "2_2") (pintype "passive"))
      (node (ref "U1") (pin "16") (pinfunction "GPIO13_16") (pintype "bidirectional"))
    )
    (net (code "60") (name "V1P1") (class "Default")
      (node (ref "C13") (pin "1") (pinfunction "1_1") (pintype "passive"))
      (node (ref "C16") (pin "1") (pinfunction "1_1") (pintype "passive"))
      (node (ref "C17") (pin "1") (pinfunction "1_1") (pintype "passive"))
      (node (ref "TP4") (pin "P$1") (pinfunction "P$1_P$1") (pintype "bidirectional"))
      (node (ref "U1") (pin "23") (pinfunction "DVDD_23") (pintype "power_in"))
      (node (ref "U1") (pin "45") (pinfunction "VREG_VOUT_45") (pintype "power_in"))
      (node (ref "U1") (pin "50") (pinfunction "DVDD_50") (pintype "power_in"))
    )
    (net (code "61") (name "V3P3") (class "Default")
      (node (ref "C14") (pin "1") (pinfunction "1_1") (pintype "passive"))
      (node (ref "C18") (pin "1") (pinfunction "1_1") (pintype "passive"))
      (node (ref "C19") (pin "1") (pinfunction "1_1") (pintype "passive"))
      (node (ref "C20") (pin "1") (pinfunction "1_1") (pintype "passive"))
      (node (ref "C21") (pin "1") (pinfunction "1_1") (pintype "passive"))
      (node (ref "C22") (pin "1") (pinfunction "1_1") (pintype "passive"))
      (node (ref "C23") (pin "1") (pinfunction "1_1") (pintype "passive"))
      (node (ref "C4") (pin "1") (pinfunction "1_1") (pintype "passive"))
      (node (ref "C5") (pin "1") (pinfunction "1_1") (pintype "passive"))
      (node (ref "C6") (pin "1") (pinfunction "1_1") (pintype "passive"))
      (node (ref "D1") (pin "6") (pinfunction "VP_6") (pintype "power_in"))
      (node (ref "D2") (pin "6") (pinfunction "VP_6") (pintype "power_in"))
      (node (ref "D3") (pin "6") (pinfunction "VP_6") (pintype "power_in"))
      (node (ref "D4") (pin "6") (pinfunction "VP_6") (pintype "power_in"))
      (node (ref "D5") (pin "6") (pinfunction "VP_6") (pintype "power_in"))
      (node (ref "D6") (pin "6") (pinfunction "VP_6") (pintype "power_in"))
      (node (ref "D7") (pin "6") (pinfunction "VP_6") (pintype "power_in"))
      (node (ref "D8") (pin "6") (pinfunction "VP_6") (pintype "power_in"))
      (node (ref "J2") (pin "B16") (pinfunction "31_B16") (pintype "passive"))
      (node (ref "R17") (pin "2") (pinfunction "2_2") (pintype "passive"))
      (node (ref "R18") (pin "2") (pinfunction "2_2") (pintype "passive"))
      (node (ref "R23") (pin "1") (pinfunction "1_1") (pintype "passive"))
      (node (ref "TP2") (pin "P$1") (pinfunction "P$1_P$1") (pintype "bidirectional"))
      (node (ref "U1") (pin "1") (pinfunction "IOVDD_1") (pintype "power_in"))
      (node (ref "U1") (pin "10") (pinfunction "IOVDD_10") (pintype "power_in"))
      (node (ref "U1") (pin "22") (pinfunction "IOVDD_22") (pintype "power_in"))
      (node (ref "U1") (pin "33") (pinfunction "IOVDD_33") (pintype "power_in"))
      (node (ref "U1") (pin "42") (pinfunction "IOVDD_42") (pintype "power_in"))
      (node (ref "U1") (pin "44") (pinfunction "VREG_VIN_44") (pintype "power_in"))
      (node (ref "U1") (pin "48") (pinfunction "USB_VDD_48") (pintype "power_in"))
      (node (ref "U1") (pin "49") (pinfunction "IOVDD_49") (pintype "power_in"))
      (node (ref "U2") (pin "1") (pinfunction "OUT_1") (pintype "power_in"))
      (node (ref "U3") (pin "8") (pinfunction "VCC_8") (pintype "power_in"))
    )
    (net (code "62") (name "V9P0") (class "Default")
      (node (ref "J2") (pin "A18") (pinfunction "36_A18") (pintype "passive"))
      (node (ref "R11") (pin "1") (pinfunction "1_1") (pintype "passive"))
    )
    (net (code "63") (name "VBUS") (class "Default")
      (node (ref "D9") (pin "1") (pinfunction "A1_1") (pintype "bidirectional"))
      (node (ref "D9") (pin "2") (pinfunction "A2_2") (pintype "bidirectional"))
      (node (ref "J6") (pin "1") (pinfunction "1_1") (pintype "bidirectional"))
    )
    (net (code "64") (name "VIMU") (class "Default")
      (node (ref "C10") (pin "1") (pinfunction "1_1") (pintype "passive"))
      (node (ref "C9") (pin "1") (pinfunction "1_1") (pintype "passive"))
      (node (ref "J1") (pin "1") (pinfunction "1_1") (pintype "passive"))
      (node (ref "J1") (pin "3") (pinfunction "3_3") (pintype "passive"))
      (node (ref "J3") (pin "1") (pinfunction "1_1") (pintype "passive"))
      (node (ref "R12") (pin "2") (pinfunction "2_2") (pintype "passive"))
      (node (ref "TP3") (pin "P$1") (pinfunction "P$1_P$1") (pintype "bidirectional"))
      (node (ref "U4") (pin "6") (pinfunction "OUT_6") (pintype "power_in"))
    )
    (net (code "65") (name "VIMU_EN") (class "Default")
      (node (ref "R19") (pin "2") (pinfunction "2_2") (pintype "passive"))
      (node (ref "U1") (pin "13") (pinfunction "GPIO10_13") (pintype "bidirectional"))
      (node (ref "U4") (pin "3") (pinfunction "EN_3") (pintype "input"))
    )
    (net (code "66") (name "VIN") (class "Default")
      (node (ref "C2") (pin "1") (pinfunction "1_1") (pintype "passive"))
      (node (ref "C3") (pin "1") (pinfunction "1_1") (pintype "passive"))
      (node (ref "C7") (pin "1") (pinfunction "1_1") (pintype "passive"))
      (node (ref "C8") (pin "1") (pinfunction "1_1") (pintype "passive"))
      (node (ref "D10") (pin "3") (pinfunction "C_3") (pintype "bidirectional"))
      (node (ref "D9") (pin "3") (pinfunction "C_3") (pintype "bidirectional"))
      (node (ref "TP1") (pin "P$1") (pinfunction "P$1_P$1") (pintype "bidirectional"))
      (node (ref "U2") (pin "5") (pinfunction "/SHDN_5") (pintype "input"))
      (node (ref "U2") (pin "8") (pinfunction "IN_8") (pintype "power_in"))
      (node (ref "U4") (pin "1") (pinfunction "IN_1") (pintype "power_in"))
    )
    (net (code "67") (name "VIN_BP") (class "Default")
      (node (ref "D10") (pin "1") (pinfunction "A1_1") (pintype "bidirectional"))
      (node (ref "D10") (pin "2") (pinfunction "A2_2") (pintype "bidirectional"))
      (node (ref "J2") (pin "A1") (pinfunction "2_A1") (pintype "passive"))
      (node (ref "J2") (pin "A3") (pinfunction "6_A3") (pintype "passive"))
      (node (ref "J2") (pin "B1") (pinfunction "1_B1") (pintype "passive"))
      (node (ref "J2") (pin "B3") (pinfunction "5_B3") (pintype "passive"))
    )
    (net (code "68") (name "VIN_SENSE") (class "Default")
      (node (ref "C1") (pin "1") (pinfunction "1_1") (pintype "passive"))
      (node (ref "R12") (pin "1") (pinfunction "1_1") (pintype "passive"))
      (node (ref "R15") (pin "2") (pinfunction "2_2") (pintype "passive"))
      (node (ref "U1") (pin "41") (pinfunction "GPIO29/ADC3_41") (pintype "bidirectional"))
    )
    (net (code "69") (name "VN3P0") (class "Default")
      (node (ref "J2") (pin "A19") (pinfunction "38_A19") (pintype "passive"))
      (node (ref "R13") (pin "1") (pinfunction "1_1") (pintype "passive"))
    )
    (net (code "70") (name "VN22") (class "Default")
      (node (ref "J2") (pin "B20") (pinfunction "39_B20") (pintype "passive"))
      (node (ref "R14") (pin "1") (pinfunction "1_1") (pintype "passive"))
    )
    (net (code "71") (name "unconnected-(D6-CH2-Pad4)") (class "Default")
      (node (ref "D6") (pin "4") (pinfunction "CH2_4") (pintype "bidirectional"))
    )
    (net (code "72") (name "unconnected-(J1-Pad5)") (class "Default")
      (node (ref "J1") (pin "5") (pinfunction "5_5") (pintype "passive"))
    )
    (net (code "73") (name "unconnected-(J1-Pad21)") (class "Default")
      (node (ref "J1") (pin "21") (pinfunction "21_21") (pintype "passive"))
    )
    (net (code "74") (name "unconnected-(J6-Pad4)") (class "Default")
      (node (ref "J6") (pin "4") (pinfunction "4_4") (pintype "bidirectional"))
    )
    (net (code "75") (name "unconnected-(U1A-GPIO09-Pad12)") (class "Default")
      (node (ref "U1") (pin "12") (pinfunction "GPIO09_12") (pintype "bidirectional"))
    )
    (net (code "76") (name "unconnected-(U1A-GPIO11-Pad14)") (class "Default")
      (node (ref "U1") (pin "14") (pinfunction "GPIO11_14") (pintype "bidirectional"))
    )
    (net (code "77") (name "unconnected-(U2-PWRGD-Pad2)") (class "Default")
      (node (ref "U2") (pin "2") (pinfunction "PWRGD_2") (pintype "output"))
    )
    (net (code "78") (name "unconnected-(U4-FAULT#-Pad4)") (class "Default")
      (node (ref "U4") (pin "4") (pinfunction "FAULT#_4") (pintype "open_collector"))
    )
  )
)
